# wifi.net
KiCad netlist of a schematic drawn in Altium Designer
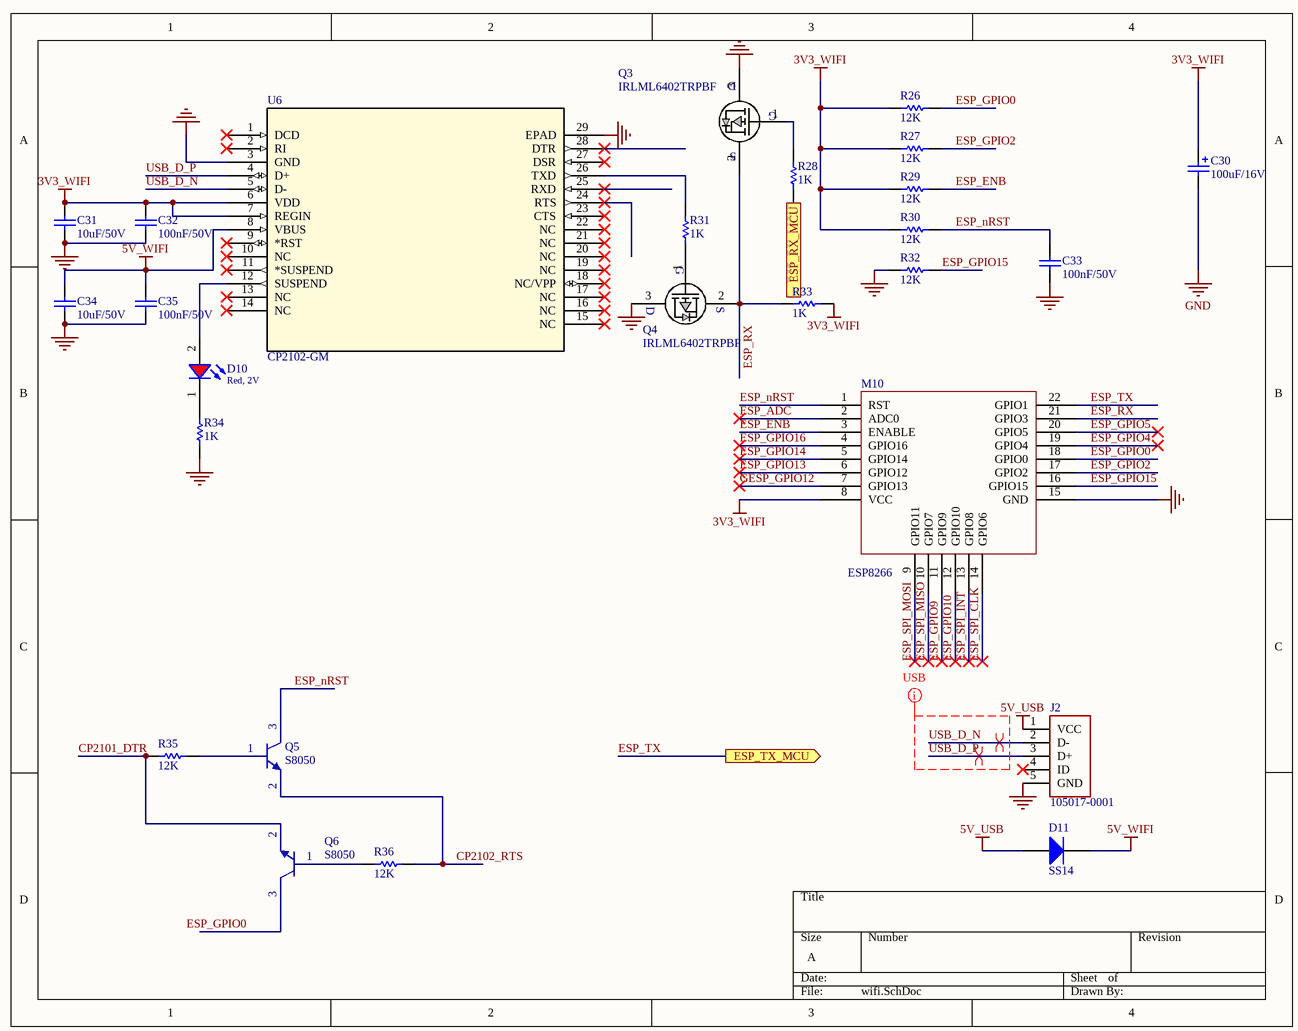
[diagram p0: wifi.SchDoc]

(export (version "E")
  (design (tool "Eeschema 10.0.6"))
  (components
    (comp (ref "C30")
      (value "100uF/16V")
      (footprint "CAP_SM_TAN")
      (fields
        (field (name "MANUFACTURER") "Nichicon")
        (field (name "MANUFACTURER PART NUMBER") "UWX1C101MCL1GB")
        (field (name "Comment") "TAJB107M006RNJ")
      )
      (libsource (lib "Capacitor") (part "Cap-Tan-100uF-16V"))
    )
    (comp (ref "C31")
      (value "10uF/50V")
      (footprint "CAP-SM-0805")
      (description "CAP CER 10UF 50V X5R 0805")
      (fields
        (field (name "MANUFACTURER") "Yageo")
        (field (name "MANUFACTURER PART NUMBER") "CC0805KKX5R9BB106")
      )
      (libsource (lib "Capacitor") (part "Cap-10uF-50V-0805"))
    )
    (comp (ref "C32")
      (value "100nF/50V")
      (footprint "CAP-SM-0805")
      (description "CAP CER 0.1UF 50V Y5V 0805")
      (fields
        (field (name "MANUFACTURER") "Samsung Electro-Mechanics")
        (field (name "MANUFACTURER PART NUMBER") "CL21F104ZBCNNNC")
      )
      (libsource (lib "Capacitor") (part "Cap-100nF-50V-0805"))
    )
    (comp (ref "C33")
      (value "100nF/50V")
      (footprint "CAP-SM-0805")
      (description "CAP CER 0.1UF 50V Y5V 0805")
      (fields
        (field (name "MANUFACTURER") "Samsung Electro-Mechanics")
        (field (name "MANUFACTURER PART NUMBER") "CL21F104ZBCNNNC")
      )
      (libsource (lib "Capacitor") (part "Cap-100nF-50V-0805"))
    )
    (comp (ref "C34")
      (value "10uF/50V")
      (footprint "CAP-SM-0805")
      (description "CAP CER 10UF 50V X5R 0805")
      (fields
        (field (name "MANUFACTURER") "Yageo")
        (field (name "MANUFACTURER PART NUMBER") "CC0805KKX5R9BB106")
      )
      (libsource (lib "Capacitor") (part "Cap-10uF-50V-0805"))
    )
    (comp (ref "C35")
      (value "100nF/50V")
      (footprint "CAP-SM-0805")
      (description "CAP CER 0.1UF 50V Y5V 0805")
      (fields
        (field (name "MANUFACTURER") "Samsung Electro-Mechanics")
        (field (name "MANUFACTURER PART NUMBER") "CL21F104ZBCNNNC")
      )
      (libsource (lib "Capacitor") (part "Cap-100nF-50V-0805"))
    )
    (comp (ref "D10")
      (value "Red, 2V")
      (footprint "WL-SMCW_0805")
      (description "WL-SMCW SMT Mono-color Chip LED Waterclear, size 0805, Red, 2V, 140deg")
      (fields (field (name "PART NUMBER") "150080RS75000") (field (name "PUBLISHER") "Wurth Elektronik"))
      (libsource (lib "150080BS75000_Altium_WL-SMCW_rev20a") (part "150080RS75000"))
    )
    (comp (ref "D11")
      (value "SS14")
      (footprint "SS14")
      (description "DIODE SCHOTTKY 40V 1A SMA")
      (fields (field (name "MANUFACTURER") "ON Semiconductor"))
      (libsource (lib "Diode") (part "Diode-SS14"))
    )
    (comp (ref "J2")
      (value "105017-0001")
      (footprint "CONN_105017-0001")
      (description "No Description Available")
      (fields (field (name "COPYRIGHT") "Copyright (C) 2018 Accelerated Designs. All rights reserved"))
      (libsource (lib "Header-connector") (part "105017-0001"))
    )
    (comp (ref "M10") (value "ESP8266") (footprint "ESP8266") (libsource (lib "Schlib1") (part "ESP8266")))
    (comp (ref "Q3")
      (value "IRLML6402TRPBF")
      (footprint "SOT23_NEX")
      (description "P-Channel 20V 3.7A (Ta) 1.3W (Ta) Surface Mount Micro3™/SOT-23")
      (libsource (lib "MOSFET") (part "IRLML6402TRPBF"))
    )
    (comp (ref "Q4")
      (value "IRLML6402TRPBF")
      (footprint "SOT23_NEX")
      (description "P-Channel 20V 3.7A (Ta) 1.3W (Ta) Surface Mount Micro3™/SOT-23")
      (libsource (lib "MOSFET") (part "IRLML6402TRPBF"))
    )
    (comp (ref "Q5") (value "S8050") (footprint "SOT23_NEX") (libsource (lib "BJT") (part "S8050")))
    (comp (ref "Q6") (value "S8050") (footprint "SOT23_NEX") (libsource (lib "BJT") (part "S8050")))
    (comp (ref "R26")
      (value "12K")
      (footprint "Resistor:RES-SM-0805")
      (description "RES 12 KOHM JUMPER 0805")
      (fields
        (field (name "MANUFACTURER") "Vishay Thin Film")
        (field (name "MANUFACTURER PART NUMBER") "PAT0805E3121BST1")
      )
      (libsource (lib "Resistor") (part "Res-12K-0805"))
    )
    (comp (ref "R27")
      (value "12K")
      (footprint "Resistor:RES-SM-0805")
      (description "RES 12 KOHM JUMPER 0805")
      (fields
        (field (name "MANUFACTURER") "Vishay Thin Film")
        (field (name "MANUFACTURER PART NUMBER") "PAT0805E3121BST1")
      )
      (libsource (lib "Resistor") (part "Res-12K-0805"))
    )
    (comp (ref "R28")
      (value "1K")
      (footprint "Resistor:RES-SM-0805")
      (description "RES 1K OHM 1% 1/4W 0805")
      (fields
        (field (name "MANUFACTURER") "Stackpole Electronics Inc")
        (field (name "MANUFACTURER PART NUMBER") "RNCP0805FTD1K00")
      )
      (libsource (lib "Resistor") (part "Res-1K-0805"))
    )
    (comp (ref "R29")
      (value "12K")
      (footprint "Resistor:RES-SM-0805")
      (description "RES 12 KOHM JUMPER 0805")
      (fields
        (field (name "MANUFACTURER") "Vishay Thin Film")
        (field (name "MANUFACTURER PART NUMBER") "PAT0805E3121BST1")
      )
      (libsource (lib "Resistor") (part "Res-12K-0805"))
    )
    (comp (ref "R30")
      (value "12K")
      (footprint "Resistor:RES-SM-0805")
      (description "RES 12 KOHM JUMPER 0805")
      (fields
        (field (name "MANUFACTURER") "Vishay Thin Film")
        (field (name "MANUFACTURER PART NUMBER") "PAT0805E3121BST1")
      )
      (libsource (lib "Resistor") (part "Res-12K-0805"))
    )
    (comp (ref "R31")
      (value "1K")
      (footprint "Resistor:RES-SM-0805")
      (description "RES 1K OHM 1% 1/4W 0805")
      (fields
        (field (name "MANUFACTURER") "Stackpole Electronics Inc")
        (field (name "MANUFACTURER PART NUMBER") "RNCP0805FTD1K00")
      )
      (libsource (lib "Resistor") (part "Res-1K-0805"))
    )
    (comp (ref "R32")
      (value "12K")
      (footprint "Resistor:RES-SM-0805")
      (description "RES 12 KOHM JUMPER 0805")
      (fields
        (field (name "MANUFACTURER") "Vishay Thin Film")
        (field (name "MANUFACTURER PART NUMBER") "PAT0805E3121BST1")
      )
      (libsource (lib "Resistor") (part "Res-12K-0805"))
    )
    (comp (ref "R33")
      (value "1K")
      (footprint "Resistor:RES-SM-0805")
      (description "RES 1K OHM 1% 1/4W 0805")
      (fields
        (field (name "MANUFACTURER") "Stackpole Electronics Inc")
        (field (name "MANUFACTURER PART NUMBER") "RNCP0805FTD1K00")
      )
      (libsource (lib "Resistor") (part "Res-1K-0805"))
    )
    (comp (ref "R34")
      (value "1K")
      (footprint "Resistor:RES-SM-0805")
      (description "RES 1K OHM 1% 1/4W 0805")
      (fields
        (field (name "MANUFACTURER") "Stackpole Electronics Inc")
        (field (name "MANUFACTURER PART NUMBER") "RNCP0805FTD1K00")
      )
      (libsource (lib "Resistor") (part "Res-1K-0805"))
    )
    (comp (ref "R35")
      (value "12K")
      (footprint "Resistor:RES-SM-0805")
      (description "RES 12 KOHM JUMPER 0805")
      (fields
        (field (name "MANUFACTURER") "Vishay Thin Film")
        (field (name "MANUFACTURER PART NUMBER") "PAT0805E3121BST1")
      )
      (libsource (lib "Resistor") (part "Res-12K-0805"))
    )
    (comp (ref "R36")
      (value "12K")
      (footprint "Resistor:RES-SM-0805")
      (description "RES 12 KOHM JUMPER 0805")
      (fields
        (field (name "MANUFACTURER") "Vishay Thin Film")
        (field (name "MANUFACTURER PART NUMBER") "PAT0805E3121BST1")
      )
      (libsource (lib "Resistor") (part "Res-12K-0805"))
    )
    (comp (ref "U6")
      (value "CP2102-GM")
      (footprint "CP2102-GM")
      (description "No Description Available")
      (fields (field (name "COPYRIGHT") "Copyright (C) 2018 Accelerated Designs. All rights reserved"))
      (libsource (lib "Schlib1") (part "CP2102-GM"))
    )
  )
  (nets
    (net (code "1") (name "/CP2101_DTR") (class "Default")
      (node (ref "Q6") (pin "2") (pinfunction "E_2") (pintype "passive"))
      (node (ref "R35") (pin "1") (pinfunction "1_1") (pintype "passive"))
    )
    (net (code "2") (name "/CP2102_RTS") (class "Default")
      (node (ref "Q5") (pin "2") (pinfunction "E_2") (pintype "passive"))
      (node (ref "R36") (pin "2") (pinfunction "2_2") (pintype "passive"))
    )
    (net (code "3") (name "/ESP_ADC") (class "Default")
      (node (ref "M10") (pin "2") (pinfunction "ADC0_2") (pintype "passive+no_connect"))
    )
    (net (code "4") (name "/ESP_ENB") (class "Default")
      (node (ref "M10") (pin "3") (pinfunction "ENABLE_3") (pintype "passive"))
      (node (ref "R29") (pin "2") (pinfunction "2_2") (pintype "passive"))
    )
    (net (code "5") (name "/ESP_GPIO0") (class "Default")
      (node (ref "M10") (pin "18") (pinfunction "GPIO0_18") (pintype "passive"))
      (node (ref "R26") (pin "2") (pinfunction "2_2") (pintype "passive"))
    )
    (net (code "6") (name "/ESP_GPIO2") (class "Default")
      (node (ref "M10") (pin "17") (pinfunction "GPIO2_17") (pintype "passive"))
      (node (ref "R27") (pin "2") (pinfunction "2_2") (pintype "passive"))
    )
    (net (code "7") (name "/ESP_GPIO4") (class "Default")
      (node (ref "M10") (pin "19") (pinfunction "GPIO4_19") (pintype "passive+no_connect"))
    )
    (net (code "8") (name "/ESP_GPIO5") (class "Default")
      (node (ref "M10") (pin "20") (pinfunction "GPIO5_20") (pintype "passive+no_connect"))
    )
    (net (code "9") (name "/ESP_GPIO9") (class "Default")
      (node (ref "M10") (pin "11") (pinfunction "GPIO9_11") (pintype "passive+no_connect"))
    )
    (net (code "10") (name "/ESP_GPIO10") (class "Default")
      (node (ref "M10") (pin "12") (pinfunction "GPIO10_12") (pintype "passive+no_connect"))
    )
    (net (code "11") (name "/ESP_GPIO13") (class "Default")
      (node (ref "M10") (pin "6") (pinfunction "GPIO12_6") (pintype "passive+no_connect"))
    )
    (net (code "12") (name "/ESP_GPIO14") (class "Default")
      (node (ref "M10") (pin "5") (pinfunction "GPIO14_5") (pintype "passive+no_connect"))
    )
    (net (code "13") (name "/ESP_GPIO15") (class "Default")
      (node (ref "M10") (pin "16") (pinfunction "GPIO15_16") (pintype "passive"))
      (node (ref "R32") (pin "2") (pinfunction "2_2") (pintype "passive"))
    )
    (net (code "14") (name "/ESP_GPIO16") (class "Default")
      (node (ref "M10") (pin "4") (pinfunction "GPIO16_4") (pintype "passive+no_connect"))
    )
    (net (code "15") (name "/ESP_RX") (class "Default")
      (node (ref "M10") (pin "21") (pinfunction "GPIO3_21") (pintype "passive"))
      (node (ref "Q3") (pin "2") (pinfunction "S_2") (pintype "passive"))
      (node (ref "Q4") (pin "2") (pinfunction "S_2") (pintype "passive"))
      (node (ref "R33") (pin "1") (pinfunction "1_1") (pintype "passive"))
    )
    (net (code "16") (name "/ESP_RX_MCU") (class "Default")
      (node (ref "R28") (pin "1") (pinfunction "1_1") (pintype "passive"))
    )
    (net (code "17") (name "/ESP_SPI_CLK") (class "Default")
      (node (ref "M10") (pin "14") (pinfunction "GPIO6_14") (pintype "passive+no_connect"))
    )
    (net (code "18") (name "/ESP_SPI_INT") (class "Default")
      (node (ref "M10") (pin "13") (pinfunction "GPIO8_13") (pintype "passive+no_connect"))
    )
    (net (code "19") (name "/ESP_SPI_MISO") (class "Default")
      (node (ref "M10") (pin "10") (pinfunction "GPIO7_10") (pintype "passive+no_connect"))
    )
    (net (code "20") (name "/ESP_SPI_MOSI") (class "Default")
      (node (ref "M10") (pin "9") (pinfunction "GPIO11_9") (pintype "passive+no_connect"))
    )
    (net (code "21") (name "/ESP_TX") (class "Default")
      (node (ref "M10") (pin "22") (pinfunction "GPIO1_22") (pintype "passive"))
    )
    (net (code "22") (name "/ESP_nRST") (class "Default")
      (node (ref "C33") (pin "2") (pinfunction "2_2") (pintype "passive"))
      (node (ref "M10") (pin "1") (pinfunction "RST_1") (pintype "passive"))
      (node (ref "Q5") (pin "3") (pinfunction "C_3") (pintype "passive"))
      (node (ref "R30") (pin "2") (pinfunction "2_2") (pintype "passive"))
    )
    (net (code "23") (name "/GESP_GPIO12") (class "Default")
      (node (ref "M10") (pin "7") (pinfunction "GPIO13_7") (pintype "passive+no_connect"))
    )
    (net (code "24") (name "/USB_D_N") (class "Default")
      (node (ref "J2") (pin "2") (pinfunction "D-_2") (pintype "passive"))
      (node (ref "U6") (pin "5") (pinfunction "D-_5") (pintype "bidirectional"))
    )
    (net (code "25") (name "/USB_D_P") (class "Default")
      (node (ref "J2") (pin "3") (pinfunction "D+_3") (pintype "passive"))
      (node (ref "U6") (pin "4") (pinfunction "D+_4") (pintype "bidirectional"))
    )
    (net (code "26") (name "3V3_WIFI") (class "Default")
      (node (ref "C30") (pin "1") (pinfunction "1_1") (pintype "passive"))
      (node (ref "C31") (pin "2") (pinfunction "2_2") (pintype "passive"))
      (node (ref "C32") (pin "2") (pinfunction "2_2") (pintype "passive"))
      (node (ref "M10") (pin "8") (pinfunction "VCC_8") (pintype "passive"))
      (node (ref "R26") (pin "1") (pinfunction "1_1") (pintype "passive"))
      (node (ref "R27") (pin "1") (pinfunction "1_1") (pintype "passive"))
      (node (ref "R29") (pin "1") (pinfunction "1_1") (pintype "passive"))
      (node (ref "R30") (pin "1") (pinfunction "1_1") (pintype "passive"))
      (node (ref "R33") (pin "2") (pinfunction "2_2") (pintype "passive"))
      (node (ref "U6") (pin "6") (pinfunction "VDD_6") (pintype "power_in"))
      (node (ref "U6") (pin "7") (pinfunction "REGIN_7") (pintype "input"))
    )
    (net (code "27") (name "5V_USB") (class "Default")
      (node (ref "D11") (pin "2") (pinfunction "A_2") (pintype "passive"))
      (node (ref "J2") (pin "1") (pinfunction "VCC_1") (pintype "passive"))
    )
    (net (code "28") (name "5V_WIFI") (class "Default")
      (node (ref "C34") (pin "2") (pinfunction "2_2") (pintype "passive"))
      (node (ref "C35") (pin "1") (pinfunction "1_1") (pintype "passive"))
      (node (ref "D11") (pin "1") (pinfunction "K_1") (pintype "passive"))
      (node (ref "U6") (pin "8") (pinfunction "VBUS_8") (pintype "input"))
    )
    (net (code "29") (name "GND") (class "Default")
      (node (ref "C30") (pin "2") (pinfunction "2_2") (pintype "passive"))
      (node (ref "C31") (pin "1") (pinfunction "1_1") (pintype "passive"))
      (node (ref "C32") (pin "1") (pinfunction "1_1") (pintype "passive"))
      (node (ref "C33") (pin "1") (pinfunction "1_1") (pintype "passive"))
      (node (ref "C34") (pin "1") (pinfunction "1_1") (pintype "passive"))
      (node (ref "C35") (pin "2") (pinfunction "2_2") (pintype "passive"))
      (node (ref "J2") (pin "5") (pinfunction "GND_5") (pintype "passive"))
      (node (ref "M10") (pin "15") (pinfunction "GND_15") (pintype "passive"))
      (node (ref "Q3") (pin "3") (pinfunction "D_3") (pintype "passive"))
      (node (ref "Q4") (pin "3") (pinfunction "D_3") (pintype "passive"))
      (node (ref "R32") (pin "1") (pinfunction "1_1") (pintype "passive"))
      (node (ref "R34") (pin "1") (pinfunction "1_1") (pintype "passive"))
      (node (ref "U6") (pin "29") (pinfunction "EPAD_29") (pintype "passive"))
      (node (ref "U6") (pin "3") (pinfunction "GND_3") (pintype "power_in"))
    )
    (net (code "30") (name "Net-(D10-A)") (class "Default")
      (node (ref "D10") (pin "2") (pinfunction "A_2") (pintype "passive"))
      (node (ref "U6") (pin "12") (pinfunction "SUSPEND_12") (pintype "output"))
    )
    (net (code "31") (name "Net-(D10-K)") (class "Default")
      (node (ref "D10") (pin "1") (pinfunction "K_1") (pintype "passive"))
      (node (ref "R34") (pin "2") (pinfunction "2_2") (pintype "passive"))
    )
    (net (code "32") (name "Net-(Q3-G)") (class "Default")
      (node (ref "Q3") (pin "1") (pinfunction "G_1") (pintype "passive"))
      (node (ref "R28") (pin "2") (pinfunction "2_2") (pintype "passive"))
    )
    (net (code "33") (name "Net-(Q4-G)") (class "Default")
      (node (ref "Q4") (pin "1") (pinfunction "G_1") (pintype "passive"))
      (node (ref "R31") (pin "1") (pinfunction "1_1") (pintype "passive"))
    )
    (net (code "34") (name "Net-(Q5-B)") (class "Default")
      (node (ref "Q5") (pin "1") (pinfunction "B_1") (pintype "passive"))
      (node (ref "R35") (pin "2") (pinfunction "2_2") (pintype "passive"))
    )
    (net (code "35") (name "Net-(Q6-B)") (class "Default")
      (node (ref "Q6") (pin "1") (pinfunction "B_1") (pintype "passive"))
      (node (ref "R36") (pin "1") (pinfunction "1_1") (pintype "passive"))
    )
    (net (code "36") (name "Net-(U6-TXD)") (class "Default")
      (node (ref "R31") (pin "2") (pinfunction "2_2") (pintype "passive"))
      (node (ref "U6") (pin "26") (pinfunction "TXD_26") (pintype "output"))
    )
    (net (code "37") (name "unconnected-(J2-ID-Pad4)") (class "Default")
      (node (ref "J2") (pin "4") (pinfunction "ID_4") (pintype "passive+no_connect"))
    )
    (net (code "38") (name "unconnected-(Q6-C-Pad3)") (class "Default")
      (node (ref "Q6") (pin "3") (pinfunction "C_3") (pintype "passive"))
    )
    (net (code "39") (name "unconnected-(U6-*RST-Pad9)") (class "Default")
      (node (ref "U6") (pin "9") (pinfunction "*RST_9") (pintype "bidirectional+no_connect"))
    )
    (net (code "40") (name "unconnected-(U6-*SUSPEND-Pad11)") (class "Default")
      (node (ref "U6") (pin "11") (pinfunction "*SUSPEND_11") (pintype "output+no_connect"))
    )
    (net (code "41") (name "unconnected-(U6-CTS-Pad23)") (class "Default")
      (node (ref "U6") (pin "23") (pinfunction "CTS_23") (pintype "input+no_connect"))
    )
    (net (code "42") (name "unconnected-(U6-DCD-Pad1)") (class "Default")
      (node (ref "U6") (pin "1") (pinfunction "DCD_1") (pintype "input+no_connect"))
    )
    (net (code "43") (name "unconnected-(U6-DSR-Pad27)") (class "Default")
      (node (ref "U6") (pin "27") (pinfunction "DSR_27") (pintype "input+no_connect"))
    )
    (net (code "44") (name "unconnected-(U6-DTR-Pad28)") (class "Default")
      (node (ref "U6") (pin "28") (pinfunction "DTR_28") (pintype "output+no_connect"))
    )
    (net (code "45") (name "unconnected-(U6-NC-Pad10)") (class "Default")
      (node (ref "U6") (pin "10") (pinfunction "NC_10") (pintype "passive+no_connect"))
    )
    (net (code "46") (name "unconnected-(U6-NC-Pad13)") (class "Default")
      (node (ref "U6") (pin "13") (pinfunction "NC_13") (pintype "passive+no_connect"))
    )
    (net (code "47") (name "unconnected-(U6-NC-Pad14)") (class "Default")
      (node (ref "U6") (pin "14") (pinfunction "NC_14") (pintype "passive+no_connect"))
    )
    (net (code "48") (name "unconnected-(U6-NC-Pad15)") (class "Default")
      (node (ref "U6") (pin "15") (pinfunction "NC_15") (pintype "passive+no_connect"))
    )
    (net (code "49") (name "unconnected-(U6-NC-Pad16)") (class "Default")
      (node (ref "U6") (pin "16") (pinfunction "NC_16") (pintype "passive+no_connect"))
    )
    (net (code "50") (name "unconnected-(U6-NC-Pad17)") (class "Default")
      (node (ref "U6") (pin "17") (pinfunction "NC_17") (pintype "passive+no_connect"))
    )
    (net (code "51") (name "unconnected-(U6-NC-Pad19)") (class "Default")
      (node (ref "U6") (pin "19") (pinfunction "NC_19") (pintype "passive+no_connect"))
    )
    (net (code "52") (name "unconnected-(U6-NC-Pad20)") (class "Default")
      (node (ref "U6") (pin "20") (pinfunction "NC_20") (pintype "passive+no_connect"))
    )
    (net (code "53") (name "unconnected-(U6-NC-Pad21)") (class "Default")
      (node (ref "U6") (pin "21") (pinfunction "NC_21") (pintype "passive+no_connect"))
    )
    (net (code "54") (name "unconnected-(U6-NC-Pad22)") (class "Default")
      (node (ref "U6") (pin "22") (pinfunction "NC_22") (pintype "passive+no_connect"))
    )
    (net (code "55") (name "unconnected-(U6-NC{slash}VPP-Pad18)") (class "Default")
      (node (ref "U6") (pin "18") (pinfunction "NC/VPP_18") (pintype "bidirectional+no_connect"))
    )
    (net (code "56") (name "unconnected-(U6-RI-Pad2)") (class "Default")
      (node (ref "U6") (pin "2") (pinfunction "RI_2") (pintype "input+no_connect"))
    )
    (net (code "57") (name "unconnected-(U6-RTS-Pad24)") (class "Default")
      (node (ref "U6") (pin "24") (pinfunction "RTS_24") (pintype "output+no_connect"))
    )
    (net (code "58") (name "unconnected-(U6-RXD-Pad25)") (class "Default")
      (node (ref "U6") (pin "25") (pinfunction "RXD_25") (pintype "input+no_connect"))
    )
  )
)
